# 08_BB_Processor.net
KiCad netlist of a schematic drawn in Altium Designer
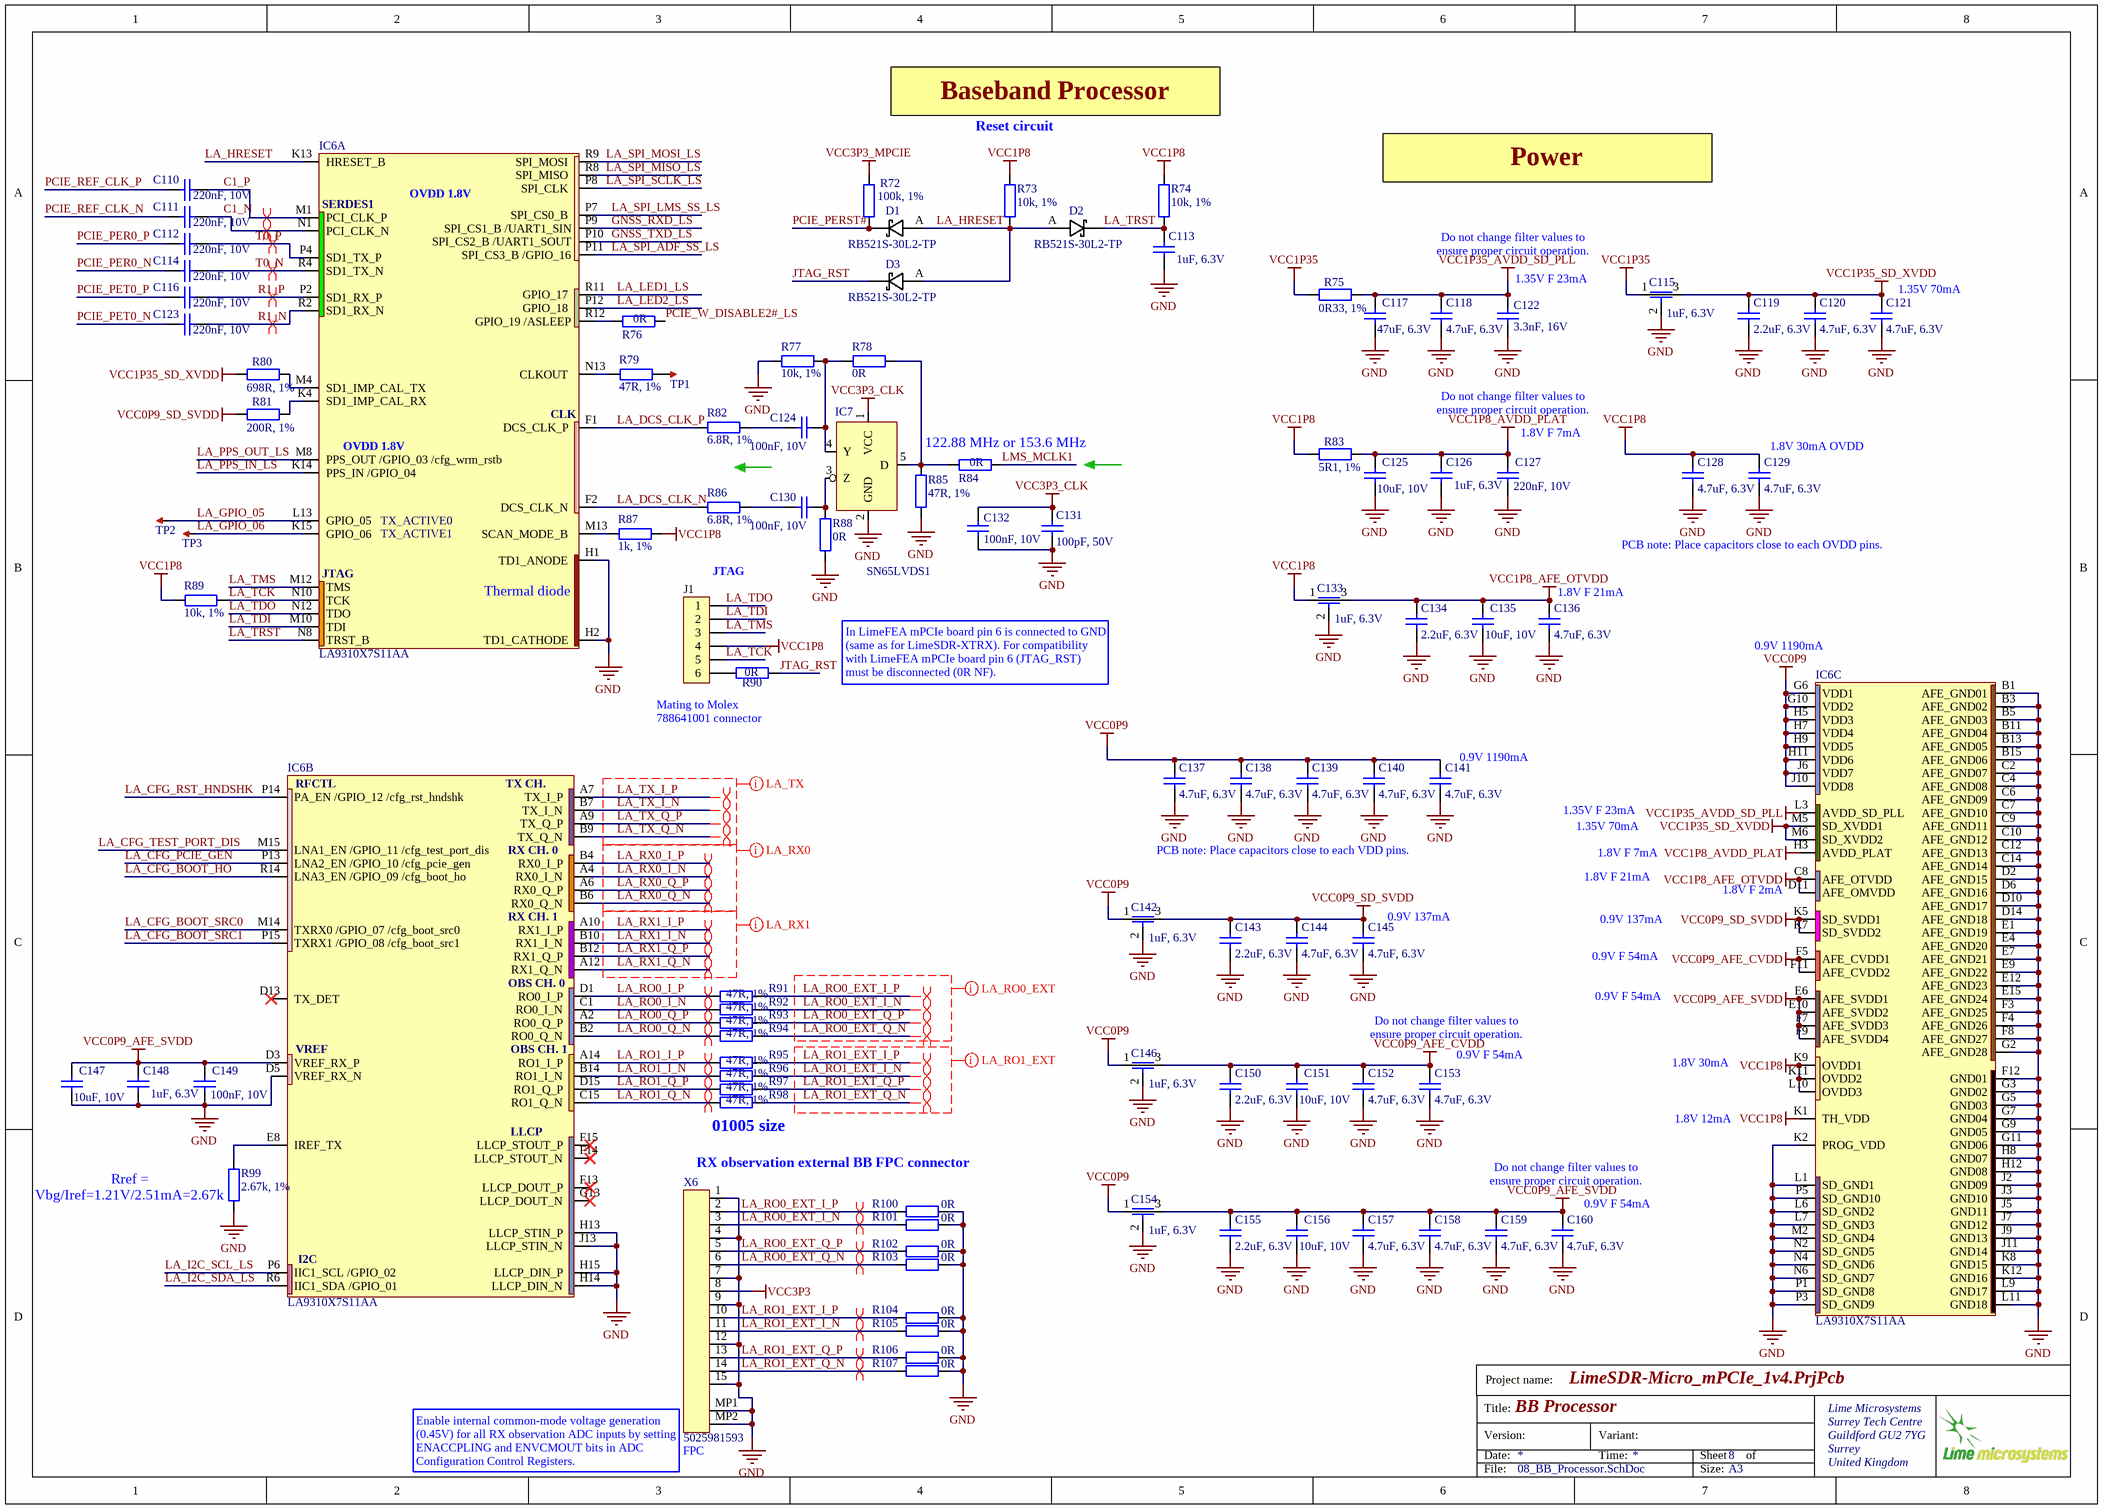
[diagram p0: 08_BB_Processor.SchDoc]

(export (version "E")
  (design (tool "Eeschema 10.0.6"))
  (components
    (comp (ref "C110")
      (value "220nF, 10V")
      (footprint "CAP0201")
      (fields
        (field (name "MANUFACTURER") "Murata")
        (field (name "TOLERANCE") "20%")
        (field (name "VOLTAGE") "10V")
      )
      (libsource (lib "LimeMicroAltiumLib_schLib") (part "Cap_0402"))
    )
    (comp (ref "C111")
      (value "220nF, 10V")
      (footprint "CAP0201")
      (fields
        (field (name "MANUFACTURER") "Murata")
        (field (name "TOLERANCE") "20%")
        (field (name "VOLTAGE") "10V")
      )
      (libsource (lib "LimeMicroAltiumLib_schLib") (part "Cap_0402"))
    )
    (comp (ref "C112")
      (value "220nF, 10V")
      (footprint "CAP0201")
      (fields
        (field (name "MANUFACTURER") "Murata")
        (field (name "TOLERANCE") "20%")
        (field (name "VOLTAGE") "10V")
      )
      (libsource (lib "LimeMicroAltiumLib_schLib") (part "Cap_0402"))
    )
    (comp (ref "C113")
      (value "1uF, 6.3V")
      (footprint "CAP0201")
      (fields (field (name "TOLERANCE") "±20%") (field (name "MANUFACTURER") "TDK Corporation"))
      (libsource (lib "LimeMicroAltiumLib_schLib") (part "Cap_0402"))
    )
    (comp (ref "C114")
      (value "220nF, 10V")
      (footprint "CAP0201")
      (fields
        (field (name "MANUFACTURER") "Murata")
        (field (name "TOLERANCE") "20%")
        (field (name "VOLTAGE") "10V")
      )
      (libsource (lib "LimeMicroAltiumLib_schLib") (part "Cap_0402"))
    )
    (comp (ref "C115")
      (value "1uF, 6.3V")
      (footprint "CAP0603_FEEDTHROUGH")
      (fields (field (name "MANUFACTURER") "TDK"))
      (libsource (lib "LimeMicroAltiumLib_schLib_r01") (part "Cap_feed_through"))
    )
    (comp (ref "C116")
      (value "220nF, 10V")
      (footprint "CAP0201")
      (fields
        (field (name "MANUFACTURER") "Murata")
        (field (name "TOLERANCE") "20%")
        (field (name "VOLTAGE") "10V")
      )
      (libsource (lib "LimeMicroAltiumLib_schLib") (part "Cap_0402"))
    )
    (comp (ref "C117")
      (value "47uF, 6.3V")
      (footprint "CAP0603")
      (fields (field (name "MANUFACTURER") "Murata") (field (name "TOLERANCE") "20%"))
      (libsource (lib "LimeFPGAboard_schLib") (part "Cap_0603"))
    )
    (comp (ref "C118")
      (value "4.7uF, 6.3V")
      (footprint "CAP0201")
      (fields (field (name "MANUFACTURER") "Murata") (field (name "TOLERANCE") "20%"))
      (libsource (lib "LimeMicroAltiumLib_schLib") (part "Cap_0402"))
    )
    (comp (ref "C119")
      (value "2.2uF, 6.3V")
      (footprint "CAP0201")
      (fields (field (name "MANUFACTURER") "Murata") (field (name "TOLERANCE") "20%"))
      (libsource (lib "LimeMicroAltiumLib_schLib") (part "Cap_0402"))
    )
    (comp (ref "C120")
      (value "4.7uF, 6.3V")
      (footprint "CAP0201")
      (fields (field (name "MANUFACTURER") "Murata") (field (name "TOLERANCE") "20%"))
      (libsource (lib "LimeMicroAltiumLib_schLib") (part "Cap_0402"))
    )
    (comp (ref "C121")
      (value "4.7uF, 6.3V")
      (footprint "CAP0201")
      (fields (field (name "MANUFACTURER") "Murata") (field (name "TOLERANCE") "20%"))
      (libsource (lib "LimeMicroAltiumLib_schLib") (part "Cap_0402"))
    )
    (comp (ref "C122")
      (value "3.3nF, 16V")
      (footprint "CAP0201")
      (fields (field (name "MANUFACTURER") "Murata"))
      (libsource (lib "LimeMicroAltiumLib_schLib") (part "Cap_0402"))
    )
    (comp (ref "C123")
      (value "220nF, 10V")
      (footprint "CAP0201")
      (fields
        (field (name "MANUFACTURER") "Murata")
        (field (name "TOLERANCE") "20%")
        (field (name "VOLTAGE") "10V")
      )
      (libsource (lib "LimeMicroAltiumLib_schLib") (part "Cap_0402"))
    )
    (comp (ref "C124")
      (value "100nF, 10V")
      (footprint "CAP0201")
      (fields (field (name "MANUFACTURER") "Samsung") (field (name "TOLERANCE") "20%"))
      (libsource (lib "LimeMicroAltiumLib_schLib") (part "Cap_0402"))
    )
    (comp (ref "C125")
      (value "10uF, 10V")
      (footprint "CAP0402")
      (fields (field (name "MANUFACTURER") "Murata"))
      (libsource (lib "LimeFPGAboard_schLib") (part "Cap_0603"))
    )
    (comp (ref "C126")
      (value "1uF, 6.3V")
      (footprint "CAP0201")
      (fields (field (name "TOLERANCE") "±20%") (field (name "MANUFACTURER") "TDK Corporation"))
      (libsource (lib "LimeMicroAltiumLib_schLib") (part "Cap_0402"))
    )
    (comp (ref "C127")
      (value "220nF, 10V")
      (footprint "CAP0201")
      (fields
        (field (name "MANUFACTURER") "Murata")
        (field (name "TOLERANCE") "20%")
        (field (name "VOLTAGE") "10V")
      )
      (libsource (lib "LimeMicroAltiumLib_schLib") (part "Cap_0402"))
    )
    (comp (ref "C128")
      (value "4.7uF, 6.3V")
      (footprint "CAP0201")
      (fields (field (name "MANUFACTURER") "Murata") (field (name "TOLERANCE") "20%"))
      (libsource (lib "LimeMicroAltiumLib_schLib") (part "Cap_0402"))
    )
    (comp (ref "C129")
      (value "4.7uF, 6.3V")
      (footprint "CAP0201")
      (fields (field (name "MANUFACTURER") "Murata") (field (name "TOLERANCE") "20%"))
      (libsource (lib "LimeMicroAltiumLib_schLib") (part "Cap_0402"))
    )
    (comp (ref "C130")
      (value "100nF, 10V")
      (footprint "CAP0201")
      (fields (field (name "MANUFACTURER") "Samsung") (field (name "TOLERANCE") "20%"))
      (libsource (lib "LimeMicroAltiumLib_schLib") (part "Cap_0402"))
    )
    (comp (ref "C131")
      (value "100pF, 50V")
      (footprint "CAP0201")
      (fields
        (field (name "MANUFACTURER") "TDK")
        (field (name "TOLERANCE") "5%")
        (field (name "VOLTAGE") "50V")
      )
      (libsource (lib "LimeMicroAltiumLib_schLib") (part "Cap_0402"))
    )
    (comp (ref "C132")
      (value "100nF, 10V")
      (footprint "CAP0201")
      (fields (field (name "MANUFACTURER") "Samsung") (field (name "TOLERANCE") "20%"))
      (libsource (lib "LimeMicroAltiumLib_schLib") (part "Cap_0402"))
    )
    (comp (ref "C133")
      (value "1uF, 6.3V")
      (footprint "CAP0603_FEEDTHROUGH")
      (fields (field (name "MANUFACTURER") "TDK"))
      (libsource (lib "LimeMicroAltiumLib_schLib_r01") (part "Cap_feed_through"))
    )
    (comp (ref "C134")
      (value "2.2uF, 6.3V")
      (footprint "CAP0201")
      (fields (field (name "MANUFACTURER") "Murata") (field (name "TOLERANCE") "20%"))
      (libsource (lib "LimeMicroAltiumLib_schLib") (part "Cap_0402"))
    )
    (comp (ref "C135")
      (value "10uF, 10V")
      (footprint "CAP0402")
      (fields (field (name "MANUFACTURER") "Murata"))
      (libsource (lib "LimeFPGAboard_schLib") (part "Cap_0603"))
    )
    (comp (ref "C136")
      (value "4.7uF, 6.3V")
      (footprint "CAP0201")
      (fields (field (name "MANUFACTURER") "Murata") (field (name "TOLERANCE") "20%"))
      (libsource (lib "LimeMicroAltiumLib_schLib") (part "Cap_0402"))
    )
    (comp (ref "C137")
      (value "4.7uF, 6.3V")
      (footprint "CAP0201")
      (fields (field (name "MANUFACTURER") "Murata") (field (name "TOLERANCE") "20%"))
      (libsource (lib "LimeMicroAltiumLib_schLib") (part "Cap_0402"))
    )
    (comp (ref "C138")
      (value "4.7uF, 6.3V")
      (footprint "CAP0201")
      (fields (field (name "MANUFACTURER") "Murata") (field (name "TOLERANCE") "20%"))
      (libsource (lib "LimeMicroAltiumLib_schLib") (part "Cap_0402"))
    )
    (comp (ref "C139")
      (value "4.7uF, 6.3V")
      (footprint "CAP0201")
      (fields (field (name "MANUFACTURER") "Murata") (field (name "TOLERANCE") "20%"))
      (libsource (lib "LimeMicroAltiumLib_schLib") (part "Cap_0402"))
    )
    (comp (ref "C140")
      (value "4.7uF, 6.3V")
      (footprint "CAP0201")
      (fields (field (name "MANUFACTURER") "Murata") (field (name "TOLERANCE") "20%"))
      (libsource (lib "LimeMicroAltiumLib_schLib") (part "Cap_0402"))
    )
    (comp (ref "C141")
      (value "4.7uF, 6.3V")
      (footprint "CAP0201")
      (fields (field (name "MANUFACTURER") "Murata") (field (name "TOLERANCE") "20%"))
      (libsource (lib "LimeMicroAltiumLib_schLib") (part "Cap_0402"))
    )
    (comp (ref "C142")
      (value "1uF, 6.3V")
      (footprint "CAP0603_FEEDTHROUGH")
      (fields (field (name "MANUFACTURER") "TDK"))
      (libsource (lib "LimeMicroAltiumLib_schLib_r01") (part "Cap_feed_through"))
    )
    (comp (ref "C143")
      (value "2.2uF, 6.3V")
      (footprint "CAP0201")
      (fields (field (name "MANUFACTURER") "Murata") (field (name "TOLERANCE") "20%"))
      (libsource (lib "LimeMicroAltiumLib_schLib") (part "Cap_0402"))
    )
    (comp (ref "C144")
      (value "4.7uF, 6.3V")
      (footprint "CAP0201")
      (fields (field (name "MANUFACTURER") "Murata") (field (name "TOLERANCE") "20%"))
      (libsource (lib "LimeMicroAltiumLib_schLib") (part "Cap_0402"))
    )
    (comp (ref "C145")
      (value "4.7uF, 6.3V")
      (footprint "CAP0201")
      (fields (field (name "MANUFACTURER") "Murata") (field (name "TOLERANCE") "20%"))
      (libsource (lib "LimeMicroAltiumLib_schLib") (part "Cap_0402"))
    )
    (comp (ref "C146")
      (value "1uF, 6.3V")
      (footprint "CAP0603_FEEDTHROUGH")
      (fields (field (name "MANUFACTURER") "TDK"))
      (libsource (lib "LimeMicroAltiumLib_schLib_r01") (part "Cap_feed_through"))
    )
    (comp (ref "C147")
      (value "10uF, 10V")
      (footprint "CAP0402")
      (fields (field (name "MANUFACTURER") "Murata"))
      (libsource (lib "LimeFPGAboard_schLib") (part "Cap_0603"))
    )
    (comp (ref "C148")
      (value "1uF, 6.3V")
      (footprint "CAP0201")
      (fields (field (name "TOLERANCE") "±20%") (field (name "MANUFACTURER") "TDK Corporation"))
      (libsource (lib "LimeMicroAltiumLib_schLib") (part "Cap_0402"))
    )
    (comp (ref "C149")
      (value "100nF, 10V")
      (footprint "CAP0201")
      (fields (field (name "MANUFACTURER") "Samsung") (field (name "TOLERANCE") "20%"))
      (libsource (lib "LimeMicroAltiumLib_schLib") (part "Cap_0402"))
    )
    (comp (ref "C150")
      (value "2.2uF, 6.3V")
      (footprint "CAP0201")
      (fields (field (name "MANUFACTURER") "Murata") (field (name "TOLERANCE") "20%"))
      (libsource (lib "LimeMicroAltiumLib_schLib") (part "Cap_0402"))
    )
    (comp (ref "C151")
      (value "10uF, 10V")
      (footprint "CAP0402")
      (fields (field (name "MANUFACTURER") "Murata"))
      (libsource (lib "LimeFPGAboard_schLib") (part "Cap_0603"))
    )
    (comp (ref "C152")
      (value "4.7uF, 6.3V")
      (footprint "CAP0201")
      (fields (field (name "MANUFACTURER") "Murata") (field (name "TOLERANCE") "20%"))
      (libsource (lib "LimeMicroAltiumLib_schLib") (part "Cap_0402"))
    )
    (comp (ref "C153")
      (value "4.7uF, 6.3V")
      (footprint "CAP0201")
      (fields (field (name "MANUFACTURER") "Murata") (field (name "TOLERANCE") "20%"))
      (libsource (lib "LimeMicroAltiumLib_schLib") (part "Cap_0402"))
    )
    (comp (ref "C154")
      (value "1uF, 6.3V")
      (footprint "CAP0603_FEEDTHROUGH")
      (fields (field (name "MANUFACTURER") "TDK"))
      (libsource (lib "LimeMicroAltiumLib_schLib_r01") (part "Cap_feed_through"))
    )
    (comp (ref "C155")
      (value "2.2uF, 6.3V")
      (footprint "CAP0201")
      (fields (field (name "MANUFACTURER") "Murata") (field (name "TOLERANCE") "20%"))
      (libsource (lib "LimeMicroAltiumLib_schLib") (part "Cap_0402"))
    )
    (comp (ref "C156")
      (value "10uF, 10V")
      (footprint "CAP0402")
      (fields (field (name "MANUFACTURER") "Murata"))
      (libsource (lib "LimeFPGAboard_schLib") (part "Cap_0603"))
    )
    (comp (ref "C157")
      (value "4.7uF, 6.3V")
      (footprint "CAP0201")
      (fields (field (name "MANUFACTURER") "Murata") (field (name "TOLERANCE") "20%"))
      (libsource (lib "LimeMicroAltiumLib_schLib") (part "Cap_0402"))
    )
    (comp (ref "C158")
      (value "4.7uF, 6.3V")
      (footprint "CAP0201")
      (fields (field (name "MANUFACTURER") "Murata") (field (name "TOLERANCE") "20%"))
      (libsource (lib "LimeMicroAltiumLib_schLib") (part "Cap_0402"))
    )
    (comp (ref "C159")
      (value "4.7uF, 6.3V")
      (footprint "CAP0201")
      (fields (field (name "MANUFACTURER") "Murata") (field (name "TOLERANCE") "20%"))
      (libsource (lib "LimeMicroAltiumLib_schLib") (part "Cap_0402"))
    )
    (comp (ref "C160")
      (value "4.7uF, 6.3V")
      (footprint "CAP0201")
      (fields (field (name "MANUFACTURER") "Murata") (field (name "TOLERANCE") "20%"))
      (libsource (lib "LimeMicroAltiumLib_schLib") (part "Cap_0402"))
    )
    (comp (ref "D1")
      (value "RB521S-30L2-TP")
      (footprint "RB521S-30L2-TP_DFN1006")
      (fields (field (name "MANUFACTURER") "MCC"))
      (libsource (lib "LimeMicroAltiumLib") (part "BAT46JFILM_shottky_diode"))
    )
    (comp (ref "D2")
      (value "RB521S-30L2-TP")
      (footprint "RB521S-30L2-TP_DFN1006")
      (fields (field (name "MANUFACTURER") "MCC"))
      (libsource (lib "LimeMicroAltiumLib") (part "BAT46JFILM_shottky_diode"))
    )
    (comp (ref "D3")
      (value "RB521S-30L2-TP")
      (footprint "RB521S-30L2-TP_DFN1006")
      (fields (field (name "MANUFACTURER") "MCC"))
      (libsource (lib "LimeMicroAltiumLib") (part "BAT46JFILM_shottky_diode"))
    )
    (comp (ref "IC6")
      (value "LA9310X7S11AA")
      (footprint "LA9310X7S11AA")
      (fields (field (name "MANUFACTURER") "NXP Semiconductors"))
      (libsource (lib "LimeMicroAltiumLib") (part "LA9310X7S11AA"))
    )
    (comp (ref "IC7")
      (value "SN65LVDS1")
      (footprint "SOT23-5_NO_SILK")
      (fields (field (name "MANUFACTURER") "TEXAS INSTRUMENTS"))
      (libsource (lib "LimeMicroAltiumLib_schLib") (part "SN65LVDS1"))
    )
    (comp (ref "J1")
      (value "Molex 0788641001")
      (footprint "Molex_0788641001_spring_contacts")
      (description "Header, 6-pin")
      (fields (field (name "MANUFACTURER") "Molex"))
      (libsource (lib "LimeMicroAltiumLib_schLib_r04") (part "Molex_0788641001_spring_contacts"))
    )
    (comp (ref "R72")
      (value "100k, 1%")
      (footprint "RES0201")
      (fields (field (name "MANUFACTURER") "Yageo") (field (name "TOLERANCE") "1%"))
      (libsource (lib "LimeFPGAboard_schLib") (part "Res_0402"))
    )
    (comp (ref "R73")
      (value "10k, 1%")
      (footprint "RES0201")
      (fields (field (name "MANUFACTURER") "Yageo") (field (name "TOLERANCE") "1%"))
      (libsource (lib "LimeFPGAboard_schLib") (part "Res_0402"))
    )
    (comp (ref "R74")
      (value "10k, 1%")
      (footprint "RES0201")
      (fields (field (name "MANUFACTURER") "Yageo") (field (name "TOLERANCE") "1%"))
      (libsource (lib "LimeFPGAboard_schLib") (part "Res_0402"))
    )
    (comp (ref "R75")
      (value "0R33, 1%")
      (footprint "RES0201")
      (fields (field (name "MANUFACTURER") "Ohmite"))
      (libsource (lib "LimeFPGAboard_schLib") (part "Res_0402"))
    )
    (comp (ref "R76")
      (value "0R")
      (footprint "RES0201")
      (fields (field (name "MANUFACTURER") "Yageo") (field (name "TOLERANCE") "5%"))
      (libsource (lib "LimeFPGAboard_schLib") (part "Res_0402"))
    )
    (comp (ref "R77")
      (value "10k, 1%")
      (footprint "RES0201")
      (fields (field (name "MANUFACTURER") "Yageo") (field (name "TOLERANCE") "1%"))
      (libsource (lib "LimeFPGAboard_schLib") (part "Res_0402"))
    )
    (comp (ref "R78")
      (value "0R")
      (footprint "RES0201")
      (fields (field (name "MANUFACTURER") "Yageo") (field (name "TOLERANCE") "5%"))
      (libsource (lib "LimeFPGAboard_schLib") (part "Res_0402"))
    )
    (comp (ref "R79")
      (value "47R, 1%")
      (footprint "RES0201")
      (fields (field (name "MANUFACTURER") "Yageo") (field (name "TOLERANCE") "1%"))
      (libsource (lib "LimeFPGAboard_schLib") (part "Res_0402"))
    )
    (comp (ref "R80")
      (value "698R, 1%")
      (footprint "RES0201")
      (fields (field (name "MANUFACTURER") "Yageo") (field (name "TOLERANCE") "1%"))
      (libsource (lib "LimeFPGAboard_schLib") (part "Res_0402"))
    )
    (comp (ref "R81")
      (value "200R, 1%")
      (footprint "RES0201")
      (fields (field (name "MANUFACTURER") "Yageo") (field (name "TOLERANCE") "1%"))
      (libsource (lib "LimeFPGAboard_schLib") (part "Res_0402"))
    )
    (comp (ref "R82")
      (value "6.8R, 1%")
      (footprint "RES0201")
      (fields (field (name "MANUFACTURER") "Yageo") (field (name "TOLERANCE") "1%"))
      (libsource (lib "LimeMicroAltiumLib_schLib") (part "Res_0402"))
    )
    (comp (ref "R83")
      (value "5R1, 1%")
      (footprint "RES0201")
      (fields (field (name "MANUFACTURER") "Yageo"))
      (libsource (lib "LimeFPGAboard_schLib") (part "Res_0402"))
    )
    (comp (ref "R84")
      (value "0R")
      (footprint "RES0201")
      (fields (field (name "MANUFACTURER") "Yageo") (field (name "TOLERANCE") "5%"))
      (libsource (lib "LimeFPGAboard_schLib") (part "Res_0402"))
    )
    (comp (ref "R85")
      (value "47R, 1%")
      (footprint "RES0201")
      (fields (field (name "MANUFACTURER") "Yageo") (field (name "TOLERANCE") "1%"))
      (libsource (lib "LimeFPGAboard_schLib") (part "Res_0402"))
    )
    (comp (ref "R86")
      (value "6.8R, 1%")
      (footprint "RES0201")
      (fields (field (name "MANUFACTURER") "Yageo") (field (name "TOLERANCE") "1%"))
      (libsource (lib "LimeMicroAltiumLib_schLib") (part "Res_0402"))
    )
    (comp (ref "R87")
      (value "1k, 1%")
      (footprint "RES0201")
      (fields (field (name "MANUFACTURER") "Yageo") (field (name "TOLERANCE") "1%"))
      (libsource (lib "LimeMicroAltiumLib_schLib") (part "Res_0402"))
    )
    (comp (ref "R88")
      (value "0R")
      (footprint "RES0201")
      (fields (field (name "MANUFACTURER") "Yageo") (field (name "TOLERANCE") "5%"))
      (libsource (lib "LimeFPGAboard_schLib") (part "Res_0402"))
    )
    (comp (ref "R89")
      (value "10k, 1%")
      (footprint "RES0201")
      (fields (field (name "MANUFACTURER") "Yageo") (field (name "TOLERANCE") "1%"))
      (libsource (lib "LimeFPGAboard_schLib") (part "Res_0402"))
    )
    (comp (ref "R90")
      (value "0R")
      (footprint "RES0201")
      (fields (field (name "MANUFACTURER") "Yageo") (field (name "TOLERANCE") "5%"))
      (libsource (lib "LimeFPGAboard_schLib") (part "Res_0402"))
    )
    (comp (ref "R91")
      (value "47R, 1%")
      (footprint "RES01005")
      (fields (field (name "MANUFACTURER") "Yageo") (field (name "TOLERANCE") "1%"))
      (libsource (lib "LimeFPGAboard_schLib") (part "Res_0402"))
    )
    (comp (ref "R92")
      (value "47R, 1%")
      (footprint "RES01005")
      (fields (field (name "MANUFACTURER") "Yageo") (field (name "TOLERANCE") "1%"))
      (libsource (lib "LimeFPGAboard_schLib") (part "Res_0402"))
    )
    (comp (ref "R93")
      (value "47R, 1%")
      (footprint "RES01005")
      (fields (field (name "MANUFACTURER") "Yageo") (field (name "TOLERANCE") "1%"))
      (libsource (lib "LimeFPGAboard_schLib") (part "Res_0402"))
    )
    (comp (ref "R94")
      (value "47R, 1%")
      (footprint "RES01005")
      (fields (field (name "MANUFACTURER") "Yageo") (field (name "TOLERANCE") "1%"))
      (libsource (lib "LimeFPGAboard_schLib") (part "Res_0402"))
    )
    (comp (ref "R95")
      (value "47R, 1%")
      (footprint "RES01005")
      (fields (field (name "MANUFACTURER") "Yageo") (field (name "TOLERANCE") "1%"))
      (libsource (lib "LimeFPGAboard_schLib") (part "Res_0402"))
    )
    (comp (ref "R96")
      (value "47R, 1%")
      (footprint "RES01005")
      (fields (field (name "MANUFACTURER") "Yageo") (field (name "TOLERANCE") "1%"))
      (libsource (lib "LimeFPGAboard_schLib") (part "Res_0402"))
    )
    (comp (ref "R97")
      (value "47R, 1%")
      (footprint "RES01005")
      (fields (field (name "MANUFACTURER") "Yageo") (field (name "TOLERANCE") "1%"))
      (libsource (lib "LimeFPGAboard_schLib") (part "Res_0402"))
    )
    (comp (ref "R98")
      (value "47R, 1%")
      (footprint "RES01005")
      (fields (field (name "MANUFACTURER") "Yageo") (field (name "TOLERANCE") "1%"))
      (libsource (lib "LimeFPGAboard_schLib") (part "Res_0402"))
    )
    (comp (ref "R99")
      (value "2.67k, 1%")
      (footprint "RES0201")
      (fields (field (name "MANUFACTURER") "Stackpole Electronics") (field (name "TOLERANCE") "1%"))
      (libsource (lib "LimeFPGAboard_schLib") (part "Res_0402"))
    )
    (comp (ref "R100")
      (value "0R")
      (footprint "RES01005")
      (fields (field (name "MANUFACTURER") "Panasonic") (field (name "TOLERANCE") "5%"))
      (libsource (lib "LimeFPGAboard_schLib") (part "Res_0402"))
    )
    (comp (ref "R101")
      (value "0R")
      (footprint "RES01005")
      (fields (field (name "MANUFACTURER") "Panasonic") (field (name "TOLERANCE") "5%"))
      (libsource (lib "LimeFPGAboard_schLib") (part "Res_0402"))
    )
    (comp (ref "R102")
      (value "0R")
      (footprint "RES01005")
      (fields (field (name "MANUFACTURER") "Panasonic") (field (name "TOLERANCE") "5%"))
      (libsource (lib "LimeFPGAboard_schLib") (part "Res_0402"))
    )
    (comp (ref "R103")
      (value "0R")
      (footprint "RES01005")
      (fields (field (name "MANUFACTURER") "Panasonic") (field (name "TOLERANCE") "5%"))
      (libsource (lib "LimeFPGAboard_schLib") (part "Res_0402"))
    )
    (comp (ref "R104")
      (value "0R")
      (footprint "RES01005")
      (fields (field (name "MANUFACTURER") "Panasonic") (field (name "TOLERANCE") "5%"))
      (libsource (lib "LimeFPGAboard_schLib") (part "Res_0402"))
    )
    (comp (ref "R105")
      (value "0R")
      (footprint "RES01005")
      (fields (field (name "MANUFACTURER") "Panasonic") (field (name "TOLERANCE") "5%"))
      (libsource (lib "LimeFPGAboard_schLib") (part "Res_0402"))
    )
    (comp (ref "R106")
      (value "0R")
      (footprint "RES01005")
      (fields (field (name "MANUFACTURER") "Panasonic") (field (name "TOLERANCE") "5%"))
      (libsource (lib "LimeFPGAboard_schLib") (part "Res_0402"))
    )
    (comp (ref "R107")
      (value "0R")
      (footprint "RES01005")
      (fields (field (name "MANUFACTURER") "Panasonic") (field (name "TOLERANCE") "5%"))
      (libsource (lib "LimeFPGAboard_schLib") (part "Res_0402"))
    )
    (comp (ref "TP1")
      (value "TESTPOINT_PAD")
      (footprint "TP_PAD_1MM")
      (description "Test Point PCB mount Miniature White")
      (libsource (lib "LimeMicroAltiumLib_schLib_r04") (part "TESTPOINT_PAD"))
    )
    (comp (ref "TP2")
      (value "TESTPOINT_PAD")
      (footprint "TP_PAD_1MM")
      (description "Test Point PCB mount Miniature White")
      (libsource (lib "LimeMicroAltiumLib_schLib_r04") (part "TESTPOINT_PAD"))
    )
    (comp (ref "TP3")
      (value "TESTPOINT_PAD")
      (footprint "TP_PAD_1MM")
      (description "Test Point PCB mount Miniature White")
      (libsource (lib "LimeMicroAltiumLib_schLib_r04") (part "TESTPOINT_PAD"))
    )
    (comp (ref "X6")
      (value "5025981593")
      (footprint "5025981593_FPC_connector")
      (fields (field (name "MANUFACTURER") "Molex"))
      (libsource (lib "LimeMicroAltiumLib_schLib_r04") (part "5025981593_FPC_connector"))
    )
  )
  (nets
    (net (code "1") (name "/C1_N") (class "Default")
      (node (ref "C111") (pin "2") (pinfunction "2_2") (pintype "passive"))
      (node (ref "IC6") (pin "N1") (pinfunction "PCI_CLK_N_N1") (pintype "power_in"))
    )
    (net (code "2") (name "/C1_P") (class "Default")
      (node (ref "C110") (pin "2") (pinfunction "2_2") (pintype "passive"))
      (node (ref "IC6") (pin "M1") (pinfunction "PCI_CLK_P_M1") (pintype "power_in"))
    )
    (net (code "3") (name "/GNSS_RXD_LS") (class "Default")
      (node (ref "IC6") (pin "P9") (pinfunction "SPI_CS1_B_/UART1_SIN_P9") (pintype "power_in"))
    )
    (net (code "4") (name "/GNSS_TXD_LS") (class "Default")
      (node (ref "IC6") (pin "P10") (pinfunction "SPI_CS2_B_/UART1_SOUT_P10") (pintype "power_in"))
    )
    (net (code "5") (name "/JTAG_RST") (class "Default")
      (node (ref "D3") (pin "C") (pinfunction "C_C") (pintype "passive"))
      (node (ref "R90") (pin "2") (pinfunction "2_2") (pintype "passive"))
    )
    (net (code "6") (name "/LA_CFG_BOOT_HO") (class "Default")
      (node (ref "IC6") (pin "R14") (pinfunction "LNA3_EN_/GPIO_09_/cfg_boot_ho_R14") (pintype "power_in"))
    )
    (net (code "7") (name "/LA_CFG_BOOT_SRC0") (class "Default")
      (node (ref "IC6") (pin "M14") (pinfunction "TXRX0_/GPIO_07_/cfg_boot_src0_M14") (pintype "power_in"))
    )
    (net (code "8") (name "/LA_CFG_BOOT_SRC1") (class "Default")
      (node (ref "IC6") (pin "P15") (pinfunction "TXRX1_/GPIO_08_/cfg_boot_src1_P15") (pintype "power_in"))
    )
    (net (code "9") (name "/LA_CFG_PCIE_GEN") (class "Default")
      (node (ref "IC6") (pin "P13") (pinfunction "LNA2_EN_/GPIO_10_/cfg_pcie_gen_P13") (pintype "power_in"))
    )
    (net (code "10") (name "/LA_CFG_RST_HNDSHK") (class "Default")
      (node (ref "IC6") (pin "P14") (pinfunction "PA_EN_/GPIO_12_/cfg_rst_hndshk_P14") (pintype "power_in"))
    )
    (net (code "11") (name "/LA_CFG_TEST_PORT_DIS") (class "Default")
      (node (ref "IC6") (pin "M15") (pinfunction "LNA1_EN_/GPIO_11_/cfg_test_port_dis_M15") (pintype "power_in"))
    )
    (net (code "12") (name "/LA_DCS_CLK_N") (class "Default")
      (node (ref "IC6") (pin "F2") (pinfunction "DCS_CLK_N_F2") (pintype "power_in"))
      (node (ref "R86") (pin "2") (pinfunction "2_2") (pintype "passive"))
    )
    (net (code "13") (name "/LA_DCS_CLK_P") (class "Default")
      (node (ref "IC6") (pin "F1") (pinfunction "DCS_CLK_P_F1") (pintype "power_in"))
      (node (ref "R82") (pin "2") (pinfunction "2_2") (pintype "passive"))
    )
    (net (code "14") (name "/LA_GPIO_05") (class "Default")
      (node (ref "IC6") (pin "L13") (pinfunction "GPIO_05_L13") (pintype "power_in"))
      (node (ref "TP2") (pin "1") (pintype "passive"))
    )
    (net (code "15") (name "/LA_GPIO_06") (class "Default")
      (node (ref "IC6") (pin "K15") (pinfunction "GPIO_06_K15") (pintype "power_in"))
      (node (ref "TP3") (pin "1") (pintype "passive"))
    )
    (net (code "16") (name "/LA_HRESET") (class "Default")
      (node (ref "D1") (pin "A") (pinfunction "A_A") (pintype "passive"))
      (node (ref "D2") (pin "A") (pinfunction "A_A") (pintype "passive"))
      (node (ref "D3") (pin "A") (pinfunction "A_A") (pintype "passive"))
      (node (ref "IC6") (pin "K13") (pinfunction "HRESET_B_K13") (pintype "power_in"))
      (node (ref "R73") (pin "2") (pinfunction "2_2") (pintype "passive"))
    )
    (net (code "17") (name "/LA_I2C_SCL_LS") (class "Default")
      (node (ref "IC6") (pin "P6") (pinfunction "IIC1_SCL_/GPIO_02_P6") (pintype "power_in"))
    )
    (net (code "18") (name "/LA_I2C_SDA_LS") (class "Default")
      (node (ref "IC6") (pin "R6") (pinfunction "IIC1_SDA_/GPIO_01_R6") (pintype "power_in"))
    )
    (net (code "19") (name "/LA_LED1_LS") (class "Default")
      (node (ref "IC6") (pin "R11") (pinfunction "GPIO_17_R11") (pintype "power_in"))
    )
    (net (code "20") (name "/LA_LED2_LS") (class "Default")
      (node (ref "IC6") (pin "P12") (pinfunction "GPIO_18_P12") (pintype "power_in"))
    )
    (net (code "21") (name "/LA_PPS_IN_LS") (class "Default")
      (node (ref "IC6") (pin "K14") (pinfunction "PPS_IN_/GPIO_04_K14") (pintype "power_in"))
    )
    (net (code "22") (name "/LA_PPS_OUT_LS") (class "Default")
      (node (ref "IC6") (pin "M8") (pinfunction "PPS_OUT_/GPIO_03_/cfg_wrm_rstb_M8") (pintype "power_in"))
    )
    (net (code "23") (name "/LA_RO0_EXT_I_N") (class "Default")
      (node (ref "R101") (pin "1") (pinfunction "1_1") (pintype "passive"))
      (node (ref "R92") (pin "2") (pinfunction "2_2") (pintype "passive"))
      (node (ref "X6") (pin "3") (pinfunction "3_3") (pintype "passive"))
    )
    (net (code "24") (name "/LA_RO0_EXT_I_P") (class "Default")
      (node (ref "R100") (pin "1") (pinfunction "1_1") (pintype "passive"))
      (node (ref "R91") (pin "2") (pinfunction "2_2") (pintype "passive"))
      (node (ref "X6") (pin "2") (pinfunction "2_2") (pintype "passive"))
    )
    (net (code "25") (name "/LA_RO0_EXT_Q_N") (class "Default")
      (node (ref "R103") (pin "1") (pinfunction "1_1") (pintype "passive"))
      (node (ref "R94") (pin "2") (pinfunction "2_2") (pintype "passive"))
      (node (ref "X6") (pin "6") (pinfunction "6_6") (pintype "passive"))
    )
    (net (code "26") (name "/LA_RO0_EXT_Q_P") (class "Default")
      (node (ref "R102") (pin "1") (pinfunction "1_1") (pintype "passive"))
      (node (ref "R93") (pin "2") (pinfunction "2_2") (pintype "passive"))
      (node (ref "X6") (pin "5") (pinfunction "5_5") (pintype "passive"))
    )
    (net (code "27") (name "/LA_RO0_I_N") (class "Default")
      (node (ref "IC6") (pin "C1") (pinfunction "RO0_I_N_C1") (pintype "power_in"))
      (node (ref "R92") (pin "1") (pinfunction "1_1") (pintype "passive"))
    )
    (net (code "28") (name "/LA_RO0_I_P") (class "Default")
      (node (ref "IC6") (pin "D1") (pinfunction "RO0_I_P_D1") (pintype "power_in"))
      (node (ref "R91") (pin "1") (pinfunction "1_1") (pintype "passive"))
    )
    (net (code "29") (name "/LA_RO0_Q_N") (class "Default")
      (node (ref "IC6") (pin "B2") (pinfunction "RO0_Q_N_B2") (pintype "power_in"))
      (node (ref "R94") (pin "1") (pinfunction "1_1") (pintype "passive"))
    )
    (net (code "30") (name "/LA_RO0_Q_P") (class "Default")
      (node (ref "IC6") (pin "A2") (pinfunction "RO0_Q_P_A2") (pintype "power_in"))
      (node (ref "R93") (pin "1") (pinfunction "1_1") (pintype "passive"))
    )
    (net (code "31") (name "/LA_RO1_EXT_I_N") (class "Default")
      (node (ref "R105") (pin "1") (pinfunction "1_1") (pintype "passive"))
      (node (ref "R96") (pin "2") (pinfunction "2_2") (pintype "passive"))
      (node (ref "X6") (pin "11") (pinfunction "11_11") (pintype "passive"))
    )
    (net (code "32") (name "/LA_RO1_EXT_I_P") (class "Default")
      (node (ref "R104") (pin "1") (pinfunction "1_1") (pintype "passive"))
      (node (ref "R95") (pin "2") (pinfunction "2_2") (pintype "passive"))
      (node (ref "X6") (pin "10") (pinfunction "10_10") (pintype "passive"))
    )
    (net (code "33") (name "/LA_RO1_EXT_Q_N") (class "Default")
      (node (ref "R107") (pin "1") (pinfunction "1_1") (pintype "passive"))
      (node (ref "R98") (pin "2") (pinfunction "2_2") (pintype "passive"))
      (node (ref "X6") (pin "14") (pinfunction "14_14") (pintype "passive"))
    )
    (net (code "34") (name "/LA_RO1_EXT_Q_P") (class "Default")
      (node (ref "R106") (pin "1") (pinfunction "1_1") (pintype "passive"))
      (node (ref "R97") (pin "2") (pinfunction "2_2") (pintype "passive"))
      (node (ref "X6") (pin "13") (pinfunction "13_13") (pintype "passive"))
    )
    (net (code "35") (name "/LA_RO1_I_N") (class "Default")
      (node (ref "IC6") (pin "B14") (pinfunction "RO1_I_N_B14") (pintype "power_in"))
      (node (ref "R96") (pin "1") (pinfunction "1_1") (pintype "passive"))
    )
    (net (code "36") (name "/LA_RO1_I_P") (class "Default")
      (node (ref "IC6") (pin "A14") (pinfunction "RO1_I_P_A14") (pintype "power_in"))
      (node (ref "R95") (pin "1") (pinfunction "1_1") (pintype "passive"))
    )
    (net (code "37") (name "/LA_RO1_Q_N") (class "Default")
      (node (ref "IC6") (pin "C15") (pinfunction "RO1_Q_N_C15") (pintype "power_in"))
      (node (ref "R98") (pin "1") (pinfunction "1_1") (pintype "passive"))
    )
    (net (code "38") (name "/LA_RO1_Q_P") (class "Default")
      (node (ref "IC6") (pin "D15") (pinfunction "RO1_Q_P_D15") (pintype "power_in"))
      (node (ref "R97") (pin "1") (pinfunction "1_1") (pintype "passive"))
    )
    (net (code "39") (name "/LA_RX0_I_N") (class "Default")
      (node (ref "IC6") (pin "A4") (pinfunction "RX0_I_N_A4") (pintype "power_in"))
    )
    (net (code "40") (name "/LA_RX0_I_P") (class "Default")
      (node (ref "IC6") (pin "B4") (pinfunction "RX0_I_P_B4") (pintype "power_in"))
    )
    (net (code "41") (name "/LA_RX0_Q_N") (class "Default")
      (node (ref "IC6") (pin "B6") (pinfunction "RX0_Q_N_B6") (pintype "power_in"))
    )
    (net (code "42") (name "/LA_RX0_Q_P") (class "Default")
      (node (ref "IC6") (pin "A6") (pinfunction "RX0_Q_P_A6") (pintype "power_in"))
    )
    (net (code "43") (name "/LA_RX1_I_N") (class "Default")
      (node (ref "IC6") (pin "B10") (pinfunction "RX1_I_N_B10") (pintype "power_in"))
    )
    (net (code "44") (name "/LA_RX1_I_P") (class "Default")
      (node (ref "IC6") (pin "A10") (pinfunction "RX1_I_P_A10") (pintype "power_in"))
    )
    (net (code "45") (name "/LA_RX1_Q_N") (class "Default")
      (node (ref "IC6") (pin "A12") (pinfunction "RX1_Q_N_A12") (pintype "power_in"))
    )
    (net (code "46") (name "/LA_RX1_Q_P") (class "Default")
      (node (ref "IC6") (pin "B12") (pinfunction "RX1_Q_P_B12") (pintype "power_in"))
    )
    (net (code "47") (name "/LA_SPI_ADF_SS_LS") (class "Default")
      (node (ref "IC6") (pin "P11") (pinfunction "SPI_CS3_B_/GPIO_16_P11") (pintype "power_in"))
    )
    (net (code "48") (name "/LA_SPI_LMS_SS_LS") (class "Default")
      (node (ref "IC6") (pin "P7") (pinfunction "SPI_CS0_B_P7") (pintype "power_in"))
    )
    (net (code "49") (name "/LA_SPI_MISO_LS") (class "Default")
      (node (ref "IC6") (pin "R8") (pinfunction "SPI_MISO_R8") (pintype "power_in"))
    )
    (net (code "50") (name "/LA_SPI_MOSI_LS") (class "Default")
      (node (ref "IC6") (pin "R9") (pinfunction "SPI_MOSI_R9") (pintype "power_in"))
    )
    (net (code "51") (name "/LA_SPI_SCLK_LS") (class "Default")
      (node (ref "IC6") (pin "P8") (pinfunction "SPI_CLK_P8") (pintype "power_in"))
    )
    (net (code "52") (name "/LA_TCK") (class "Default")
      (node (ref "IC6") (pin "N10") (pinfunction "TCK_N10") (pintype "power_in"))
      (node (ref "J1") (pin "5") (pinfunction "5_5") (pintype "passive"))
      (node (ref "R89") (pin "2") (pinfunction "2_2") (pintype "passive"))
    )
    (net (code "53") (name "/LA_TDI") (class "Default")
      (node (ref "IC6") (pin "M10") (pinfunction "TDI_M10") (pintype "power_in"))
      (node (ref "J1") (pin "2") (pinfunction "2_2") (pintype "passive"))
    )
    (net (code "54") (name "/LA_TDO") (class "Default")
      (node (ref "IC6") (pin "N12") (pinfunction "TDO_N12") (pintype "power_in"))
      (node (ref "J1") (pin "1") (pinfunction "1_1") (pintype "passive"))
    )
    (net (code "55") (name "/LA_TMS") (class "Default")
      (node (ref "IC6") (pin "M12") (pinfunction "TMS_M12") (pintype "power_in"))
      (node (ref "J1") (pin "3") (pinfunction "3_3") (pintype "passive"))
    )
    (net (code "56") (name "/LA_TRST") (class "Default")
      (node (ref "C113") (pin "1") (pinfunction "1_1") (pintype "passive"))
      (node (ref "D2") (pin "C") (pinfunction "C_C") (pintype "passive"))
      (node (ref "IC6") (pin "N8") (pinfunction "TRST_B_N8") (pintype "power_in"))
      (node (ref "R74") (pin "2") (pinfunction "2_2") (pintype "passive"))
    )
    (net (code "57") (name "/LA_TX_I_N") (class "Default")
      (node (ref "IC6") (pin "B7") (pinfunction "TX_I_N_B7") (pintype "power_in"))
    )
    (net (code "58") (name "/LA_TX_I_P") (class "Default")
      (node (ref "IC6") (pin "A7") (pinfunction "TX_I_P_A7") (pintype "power_in"))
    )
    (net (code "59") (name "/LA_TX_Q_N") (class "Default")
      (node (ref "IC6") (pin "B9") (pinfunction "TX_Q_N_B9") (pintype "power_in"))
    )
    (net (code "60") (name "/LA_TX_Q_P") (class "Default")
      (node (ref "IC6") (pin "A9") (pinfunction "TX_Q_P_A9") (pintype "power_in"))
    )
    (net (code "61") (name "/LMS_MCLK1") (class "Default")
      (node (ref "R84") (pin "1") (pinfunction "1_1") (pintype "passive"))
    )
    (net (code "62") (name "/PCIE_PER0_N") (class "Default")
      (node (ref "C114") (pin "1") (pinfunction "1_1") (pintype "passive"))
    )
    (net (code "63") (name "/PCIE_PER0_P") (class "Default")
      (node (ref "C112") (pin "1") (pinfunction "1_1") (pintype "passive"))
    )
    (net (code "64") (name "/PCIE_PERST#") (class "Default")
      (node (ref "D1") (pin "C") (pinfunction "C_C") (pintype "passive"))
      (node (ref "R72") (pin "2") (pinfunction "2_2") (pintype "passive"))
    )
    (net (code "65") (name "/PCIE_PET0_N") (class "Default")
      (node (ref "C123") (pin "1") (pinfunction "1_1") (pintype "passive"))
    )
    (net (code "66") (name "/PCIE_PET0_P") (class "Default")
      (node (ref "C116") (pin "1") (pinfunction "1_1") (pintype "passive"))
    )
    (net (code "67") (name "/PCIE_REF_CLK_N") (class "Default")
      (node (ref "C111") (pin "1") (pinfunction "1_1") (pintype "passive"))
    )
    (net (code "68") (name "/PCIE_REF_CLK_P") (class "Default")
      (node (ref "C110") (pin "1") (pinfunction "1_1") (pintype "passive"))
    )
    (net (code "69") (name "/PCIE_W_DISABLE2#_LS") (class "Default")
      (node (ref "R76") (pin "1") (pinfunction "1_1") (pintype "passive"))
    )
    (net (code "70") (name "/R1_N") (class "Default")
      (node (ref "C123") (pin "2") (pinfunction "2_2") (pintype "passive"))
      (node (ref "IC6") (pin "R2") (pinfunction "SD1_RX_N_R2") (pintype "power_in"))
    )
    (net (code "71") (name "/R1_P") (class "Default")
      (node (ref "C116") (pin "2") (pinfunction "2_2") (pintype "passive"))
      (node (ref "IC6") (pin "P2") (pinfunction "SD1_RX_P_P2") (pintype "power_in"))
    )
    (net (code "72") (name "/T0_N") (class "Default")
      (node (ref "C114") (pin "2") (pinfunction "2_2") (pintype "passive"))
      (node (ref "IC6") (pin "R4") (pinfunction "SD1_TX_N_R4") (pintype "power_in"))
    )
    (net (code "73") (name "/T0_P") (class "Default")
      (node (ref "C112") (pin "2") (pinfunction "2_2") (pintype "passive"))
      (node (ref "IC6") (pin "P4") (pinfunction "SD1_TX_P_P4") (pintype "power_in"))
    )
    (net (code "74") (name "GND") (class "Default")
      (node (ref "C113") (pin "2") (pinfunction "2_2") (pintype "passive"))
      (node (ref "C115") (pin "2") (pinfunction "2_2") (pintype "passive"))
      (node (ref "C117") (pin "1") (pinfunction "1_1") (pintype "passive"))
      (node (ref "C118") (pin "1") (pinfunction "1_1") (pintype "passive"))
      (node (ref "C119") (pin "1") (pinfunction "1_1") (pintype "passive"))
      (node (ref "C120") (pin "1") (pinfunction "1_1") (pintype "passive"))
      (node (ref "C121") (pin "1") (pinfunction "1_1") (pintype "passive"))
      (node (ref "C122") (pin "2") (pinfunction "2_2") (pintype "passive"))
      (node (ref "C125") (pin "1") (pinfunction "1_1") (pintype "passive"))
      (node (ref "C126") (pin "2") (pinfunction "2_2") (pintype "passive"))
      (node (ref "C127") (pin "2") (pinfunction "2_2") (pintype "passive"))
      (node (ref "C128") (pin "1") (pinfunction "1_1") (pintype "passive"))
      (node (ref "C129") (pin "1") (pinfunction "1_1") (pintype "passive"))
      (node (ref "C131") (pin "1") (pinfunction "1_1") (pintype "passive"))
      (node (ref "C132") (pin "2") (pinfunction "2_2") (pintype "passive"))
      (node (ref "C133") (pin "2") (pinfunction "2_2") (pintype "passive"))
      (node (ref "C134") (pin "1") (pinfunction "1_1") (pintype "passive"))
      (node (ref "C135") (pin "1") (pinfunction "1_1") (pintype "passive"))
      (node (ref "C136") (pin "1") (pinfunction "1_1") (pintype "passive"))
      (node (ref "C137") (pin "1") (pinfunction "1_1") (pintype "passive"))
      (node (ref "C138") (pin "1") (pinfunction "1_1") (pintype "passive"))
      (node (ref "C139") (pin "1") (pinfunction "1_1") (pintype "passive"))
      (node (ref "C140") (pin "1") (pinfunction "1_1") (pintype "passive"))
      (node (ref "C141") (pin "1") (pinfunction "1_1") (pintype "passive"))
      (node (ref "C142") (pin "2") (pinfunction "2_2") (pintype "passive"))
      (node (ref "C143") (pin "1") (pinfunction "1_1") (pintype "passive"))
      (node (ref "C144") (pin "1") (pinfunction "1_1") (pintype "passive"))
      (node (ref "C145") (pin "1") (pinfunction "1_1") (pintype "passive"))
      (node (ref "C146") (pin "2") (pinfunction "2_2") (pintype "passive"))
      (node (ref "C147") (pin "1") (pinfunction "1_1") (pintype "passive"))
      (node (ref "C148") (pin "2") (pinfunction "2_2") (pintype "passive"))
      (node (ref "C149") (pin "2") (pinfunction "2_2") (pintype "passive"))
      (node (ref "C150") (pin "1") (pinfunction "1_1") (pintype "passive"))
      (node (ref "C151") (pin "1") (pinfunction "1_1") (pintype "passive"))
      (node (ref "C152") (pin "1") (pinfunction "1_1") (pintype "passive"))
      (node (ref "C153") (pin "1") (pinfunction "1_1") (pintype "passive"))
      (node (ref "C154") (pin "2") (pinfunction "2_2") (pintype "passive"))
      (node (ref "C155") (pin "1") (pinfunction "1_1") (pintype "passive"))
      (node (ref "C156") (pin "1") (pinfunction "1_1") (pintype "passive"))
      (node (ref "C157") (pin "1") (pinfunction "1_1") (pintype "passive"))
      (node (ref "C158") (pin "1") (pinfunction "1_1") (pintype "passive"))
      (node (ref "C159") (pin "1") (pinfunction "1_1") (pintype "passive"))
      (node (ref "C160") (pin "1") (pinfunction "1_1") (pintype "passive"))
      (node (ref "IC6") (pin "B1") (pinfunction "AFE_GND01_B1") (pintype "power_in"))
      (node (ref "IC6") (pin "B11") (pinfunction "AFE_GND04_B11") (pintype "power_in"))
      (node (ref "IC6") (pin "B13") (pinfunction "AFE_GND05_B13") (pintype "power_in"))
      (node (ref "IC6") (pin "B15") (pinfunction "AFE_GND06_B15") (pintype "power_in"))
      (node (ref "IC6") (pin "B3") (pinfunction "AFE_GND02_B3") (pintype "power_in"))
      (node (ref "IC6") (pin "B5") (pinfunction "AFE_GND03_B5") (pintype "power_in"))
      (node (ref "IC6") (pin "C10") (pinfunction "AFE_GND12_C10") (pintype "power_in"))
      (node (ref "IC6") (pin "C12") (pinfunction "AFE_GND13_C12") (pintype "power_in"))
      (node (ref "IC6") (pin "C14") (pinfunction "AFE_GND14_C14") (pintype "power_in"))
      (node (ref "IC6") (pin "C2") (pinfunction "AFE_GND07_C2") (pintype "power_in"))
      (node (ref "IC6") (pin "C4") (pinfunction "AFE_GND08_C4") (pintype "power_in"))
      (node (ref "IC6") (pin "C6") (pinfunction "AFE_GND09_C6") (pintype "power_in"))
      (node (ref "IC6") (pin "C7") (pinfunction "AFE_GND10_C7") (pintype "power_in"))
      (node (ref "IC6") (pin "C9") (pinfunction "AFE_GND11_C9") (pintype "power_in"))
      (node (ref "IC6") (pin "D10") (pinfunction "AFE_GND17_D10") (pintype "power_in"))
      (node (ref "IC6") (pin "D14") (pinfunction "AFE_GND18_D14") (pintype "power_in"))
      (node (ref "IC6") (pin "D2") (pinfunction "AFE_GND15_D2") (pintype "power_in"))
      (node (ref "IC6") (pin "D5") (pinfunction "VREF_RX_N_D5") (pintype "power_in"))
      (node (ref "IC6") (pin "D6") (pinfunction "AFE_GND16_D6") (pintype "power_in"))
      (node (ref "IC6") (pin "E1") (pinfunction "AFE_GND19_E1") (pintype "power_in"))
      (node (ref "IC6") (pin "E12") (pinfunction "AFE_GND23_E12") (pintype "power_in"))
      (node (ref "IC6") (pin "E15") (pinfunction "AFE_GND24_E15") (pintype "power_in"))
      (node (ref "IC6") (pin "E4") (pinfunction "AFE_GND20_E4") (pintype "power_in"))
      (node (ref "IC6") (pin "E7") (pinfunction "AFE_GND21_E7") (pintype "power_in"))
      (node (ref "IC6") (pin "E9") (pinfunction "AFE_GND22_E9") (pintype "power_in"))
      (node (ref "IC6") (pin "F12") (pinfunction "GND01_F12") (pintype "power_in"))
      (node (ref "IC6") (pin "F3") (pinfunction "AFE_GND25_F3") (pintype "power_in"))
      (node (ref "IC6") (pin "F4") (pinfunction "AFE_GND26_F4") (pintype "power_in"))
      (node (ref "IC6") (pin "F8") (pinfunction "AFE_GND27_F8") (pintype "power_in"))
      (node (ref "IC6") (pin "G11") (pinfunction "GND06_G11") (pintype "power_in"))
      (node (ref "IC6") (pin "G2") (pinfunction "AFE_GND28_G2") (pintype "power_in"))
      (node (ref "IC6") (pin "G3") (pinfunction "GND02_G3") (pintype "power_in"))
      (node (ref "IC6") (pin "G5") (pinfunction "GND03_G5") (pintype "power_in"))
      (node (ref "IC6") (pin "G7") (pinfunction "GND04_G7") (pintype "power_in"))
      (node (ref "IC6") (pin "G9") (pinfunction "GND05_G9") (pintype "power_in"))
      (node (ref "IC6") (pin "H1") (pinfunction "TD1_ANODE_H1") (pintype "power_in"))
      (node (ref "IC6") (pin "H12") (pinfunction "GND08_H12") (pintype "power_in"))
      (node (ref "IC6") (pin "H13") (pinfunction "LLCP_STIN_P_H13") (pintype "power_in"))
      (node (ref "IC6") (pin "H14") (pinfunction "LLCP_DIN_N_H14") (pintype "power_in"))
      (node (ref "IC6") (pin "H15") (pinfunction "LLCP_DIN_P_H15") (pintype "power_in"))
      (node (ref "IC6") (pin "H2") (pinfunction "TD1_CATHODE_H2") (pintype "power_in"))
      (node (ref "IC6") (pin "H8") (pinfunction "GND07_H8") (pintype "power_in"))
      (node (ref "IC6") (pin "J11") (pinfunction "GND14_J11") (pintype "power_in"))
      (node (ref "IC6") (pin "J13") (pinfunction "LLCP_STIN_N_J13") (pintype "power_in"))
      (node (ref "IC6") (pin "J2") (pinfunction "GND09_J2") (pintype "power_in"))
      (node (ref "IC6") (pin "J3") (pinfunction "GND10_J3") (pintype "power_in"))
      (node (ref "IC6") (pin "J5") (pinfunction "GND11_J5") (pintype "power_in"))
      (node (ref "IC6") (pin "J7") (pinfunction "GND12_J7") (pintype "power_in"))
      (node (ref "IC6") (pin "J9") (pinfunction "GND13_J9") (pintype "power_in"))
      (node (ref "IC6") (pin "K12") (pinfunction "GND16_K12") (pintype "power_in"))
      (node (ref "IC6") (pin "K2") (pinfunction "PROG_VDD_K2") (pintype "power_in"))
      (node (ref "IC6") (pin "K8") (pinfunction "GND15_K8") (pintype "power_in"))
      (node (ref "IC6") (pin "L1") (pinfunction "SD_GND1_L1") (pintype "power_in"))
      (node (ref "IC6") (pin "L11") (pinfunction "GND18_L11") (pintype "power_in"))
      (node (ref "IC6") (pin "L6") (pinfunction "SD_GND2_L6") (pintype "power_in"))
      (node (ref "IC6") (pin "L7") (pinfunction "SD_GND3_L7") (pintype "power_in"))
      (node (ref "IC6") (pin "L9") (pinfunction "GND17_L9") (pintype "power_in"))
      (node (ref "IC6") (pin "M2") (pinfunction "SD_GND4_M2") (pintype "power_in"))
      (node (ref "IC6") (pin "N2") (pinfunction "SD_GND5_N2") (pintype "power_in"))
      (node (ref "IC6") (pin "N4") (pinfunction "SD_GND6_N4") (pintype "power_in"))
      (node (ref "IC6") (pin "N6") (pinfunction "SD_GND7_N6") (pintype "power_in"))
      (node (ref "IC6") (pin "P1") (pinfunction "SD_GND8_P1") (pintype "power_in"))
      (node (ref "IC6") (pin "P3") (pinfunction "SD_GND9_P3") (pintype "power_in"))
      (node (ref "IC6") (pin "P5") (pinfunction "SD_GND10_P5") (pintype "power_in"))
      (node (ref "IC7") (pin "2") (pinfunction "GND_2") (pintype "passive"))
      (node (ref "R100") (pin "2") (pinfunction "2_2") (pintype "passive"))
      (node (ref "R101") (pin "2") (pinfunction "2_2") (pintype "passive"))
      (node (ref "R102") (pin "2") (pinfunction "2_2") (pintype "passive"))
      (node (ref "R103") (pin "2") (pinfunction "2_2") (pintype "passive"))
      (node (ref "R104") (pin "2") (pinfunction "2_2") (pintype "passive"))
      (node (ref "R105") (pin "2") (pinfunction "2_2") (pintype "passive"))
      (node (ref "R106") (pin "2") (pinfunction "2_2") (pintype "passive"))
      (node (ref "R107") (pin "2") (pinfunction "2_2") (pintype "passive"))
      (node (ref "R77") (pin "1") (pinfunction "1_1") (pintype "passive"))
      (node (ref "R85") (pin "2") (pinfunction "2_2") (pintype "passive"))
      (node (ref "R88") (pin "1") (pinfunction "1_1") (pintype "passive"))
      (node (ref "R99") (pin "2") (pinfunction "2_2") (pintype "passive"))
      (node (ref "X6") (pin "1") (pinfunction "1_1") (pintype "passive"))
      (node (ref "X6") (pin "12") (pinfunction "12_12") (pintype "passive"))
      (node (ref "X6") (pin "15") (pinfunction "15_15") (pintype "passive"))
      (node (ref "X6") (pin "4") (pinfunction "4_4") (pintype "passive"))
      (node (ref "X6") (pin "7") (pinfunction "7_7") (pintype "passive"))
      (node (ref "X6") (pin "9") (pinfunction "9_9") (pintype "passive"))
      (node (ref "X6") (pin "MP1") (pinfunction "MP1_MP1") (pintype "passive"))
      (node (ref "X6") (pin "MP2") (pinfunction "MP2_MP2") (pintype "passive"))
    )
    (net (code "75") (name "Net-(C124-Pad1)") (class "Default")
      (node (ref "C124") (pin "1") (pinfunction "1_1") (pintype "passive"))
      (node (ref "R82") (pin "1") (pinfunction "1_1") (pintype "passive"))
    )
    (net (code "76") (name "Net-(C130-Pad1)") (class "Default")
      (node (ref "C130") (pin "1") (pinfunction "1_1") (pintype "passive"))
      (node (ref "R86") (pin "1") (pinfunction "1_1") (pintype "passive"))
    )
    (net (code "77") (name "Net-(IC6A-CLKOUT)") (class "Default")
      (node (ref "IC6") (pin "N13") (pinfunction "CLKOUT_N13") (pintype "power_in"))
      (node (ref "R79") (pin "2") (pinfunction "2_2") (pintype "passive"))
    )
    (net (code "78") (name "Net-(IC6A-GPIO_19_{slash}ASLEEP)") (class "Default")
      (node (ref "IC6") (pin "R12") (pinfunction "GPIO_19_/ASLEEP_R12") (pintype "power_in"))
      (node (ref "R76") (pin "2") (pinfunction "2_2") (pintype "passive"))
    )
    (net (code "79") (name "Net-(IC6A-SCAN_MODE_B)") (class "Default")
      (node (ref "IC6") (pin "M13") (pinfunction "SCAN_MODE_B_M13") (pintype "power_in"))
      (node (ref "R87") (pin "1") (pinfunction "1_1") (pintype "passive"))
    )
    (net (code "80") (name "Net-(IC6A-SD1_IMP_CAL_RX)") (class "Default")
      (node (ref "IC6") (pin "K4") (pinfunction "SD1_IMP_CAL_RX_K4") (pintype "power_in"))
      (node (ref "R81") (pin "1") (pinfunction "1_1") (pintype "passive"))
    )
    (net (code "81") (name "Net-(IC6A-SD1_IMP_CAL_TX)") (class "Default")
      (node (ref "IC6") (pin "M4") (pinfunction "SD1_IMP_CAL_TX_M4") (pintype "power_in"))
      (node (ref "R80") (pin "1") (pinfunction "1_1") (pintype "passive"))
    )
    (net (code "82") (name "Net-(IC6B-IREF_TX)") (class "Default")
      (node (ref "IC6") (pin "E8") (pinfunction "IREF_TX_E8") (pintype "power_in"))
      (node (ref "R99") (pin "1") (pinfunction "1_1") (pintype "passive"))
    )
    (net (code "83") (name "Net-(IC7-D)") (class "Default")
      (node (ref "IC7") (pin "5") (pinfunction "D_5") (pintype "passive"))
      (node (ref "R78") (pin "1") (pinfunction "1_1") (pintype "passive"))
      (node (ref "R84") (pin "2") (pinfunction "2_2") (pintype "passive"))
      (node (ref "R85") (pin "1") (pinfunction "1_1") (pintype "passive"))
    )
    (net (code "84") (name "Net-(IC7-Y)") (class "Default")
      (node (ref "C124") (pin "2") (pinfunction "2_2") (pintype "passive"))
      (node (ref "IC7") (pin "4") (pinfunction "Y_4") (pintype "passive"))
      (node (ref "R77") (pin "2") (pinfunction "2_2") (pintype "passive"))
      (node (ref "R78") (pin "2") (pinfunction "2_2") (pintype "passive"))
    )
    (net (code "85") (name "Net-(IC7-Z)") (class "Default")
      (node (ref "C130") (pin "2") (pinfunction "2_2") (pintype "passive"))
      (node (ref "IC7") (pin "3") (pinfunction "Z_3") (pintype "passive"))
      (node (ref "R88") (pin "2") (pinfunction "2_2") (pintype "passive"))
    )
    (net (code "86") (name "Net-(J1-Pad6)") (class "Default")
      (node (ref "J1") (pin "6") (pinfunction "6_6") (pintype "passive"))
      (node (ref "R90") (pin "1") (pinfunction "1_1") (pintype "passive"))
    )
    (net (code "87") (name "Net-(R79-Pad1)") (class "Default")
      (node (ref "R79") (pin "1") (pinfunction "1_1") (pintype "passive"))
      (node (ref "TP1") (pin "1") (pintype "passive"))
    )
    (net (code "88") (name "VCC0P9") (class "Default")
      (node (ref "C137") (pin "2") (pinfunction "2_2") (pintype "passive"))
      (node (ref "C138") (pin "2") (pinfunction "2_2") (pintype "passive"))
      (node (ref "C139") (pin "2") (pinfunction "2_2") (pintype "passive"))
      (node (ref "C140") (pin "2") (pinfunction "2_2") (pintype "passive"))
      (node (ref "C141") (pin "2") (pinfunction "2_2") (pintype "passive"))
      (node (ref "C142") (pin "1") (pinfunction "1_1") (pintype "passive"))
      (node (ref "C146") (pin "1") (pinfunction "1_1") (pintype "passive"))
      (node (ref "C154") (pin "1") (pinfunction "1_1") (pintype "passive"))
      (node (ref "IC6") (pin "G10") (pinfunction "VDD2_G10") (pintype "power_in"))
      (node (ref "IC6") (pin "G6") (pinfunction "VDD1_G6") (pintype "power_in"))
      (node (ref "IC6") (pin "H11") (pinfunction "VDD6_H11") (pintype "power_in"))
      (node (ref "IC6") (pin "H5") (pinfunction "VDD3_H5") (pintype "power_in"))
      (node (ref "IC6") (pin "H7") (pinfunction "VDD4_H7") (pintype "power_in"))
      (node (ref "IC6") (pin "H9") (pinfunction "VDD5_H9") (pintype "power_in"))
      (node (ref "IC6") (pin "J10") (pinfunction "VDD8_J10") (pintype "power_in"))
      (node (ref "IC6") (pin "J6") (pinfunction "VDD7_J6") (pintype "power_in"))
    )
    (net (code "89") (name "VCC0P9_AFE_CVDD") (class "Default")
      (node (ref "C146") (pin "3") (pinfunction "3_3") (pintype "passive"))
      (node (ref "C150") (pin "2") (pinfunction "2_2") (pintype "passive"))
      (node (ref "C151") (pin "2") (pinfunction "2_2") (pintype "passive"))
      (node (ref "C152") (pin "2") (pinfunction "2_2") (pintype "passive"))
      (node (ref "C153") (pin "2") (pinfunction "2_2") (pintype "passive"))
      (node (ref "IC6") (pin "F11") (pinfunction "AFE_CVDD2_F11") (pintype "power_in"))
      (node (ref "IC6") (pin "F5") (pinfunction "AFE_CVDD1_F5") (pintype "power_in"))
    )
    (net (code "90") (name "VCC0P9_AFE_SVDD") (class "Default")
      (node (ref "C147") (pin "2") (pinfunction "2_2") (pintype "passive"))
      (node (ref "C148") (pin "1") (pinfunction "1_1") (pintype "passive"))
      (node (ref "C149") (pin "1") (pinfunction "1_1") (pintype "passive"))
      (node (ref "C154") (pin "3") (pinfunction "3_3") (pintype "passive"))
      (node (ref "C155") (pin "2") (pinfunction "2_2") (pintype "passive"))
      (node (ref "C156") (pin "2") (pinfunction "2_2") (pintype "passive"))
      (node (ref "C157") (pin "2") (pinfunction "2_2") (pintype "passive"))
      (node (ref "C158") (pin "2") (pinfunction "2_2") (pintype "passive"))
      (node (ref "C159") (pin "2") (pinfunction "2_2") (pintype "passive"))
      (node (ref "C160") (pin "2") (pinfunction "2_2") (pintype "passive"))
      (node (ref "IC6") (pin "D3") (pinfunction "VREF_RX_P_D3") (pintype "power_in"))
      (node (ref "IC6") (pin "E10") (pinfunction "AFE_SVDD2_E10") (pintype "power_in"))
      (node (ref "IC6") (pin "E6") (pinfunction "AFE_SVDD1_E6") (pintype "power_in"))
      (node (ref "IC6") (pin "F7") (pinfunction "AFE_SVDD3_F7") (pintype "power_in"))
      (node (ref "IC6") (pin "F9") (pinfunction "AFE_SVDD4_F9") (pintype "power_in"))
    )
    (net (code "91") (name "VCC0P9_SD_SVDD") (class "Default")
      (node (ref "C142") (pin "3") (pinfunction "3_3") (pintype "passive"))
      (node (ref "C143") (pin "2") (pinfunction "2_2") (pintype "passive"))
      (node (ref "C144") (pin "2") (pinfunction "2_2") (pintype "passive"))
      (node (ref "C145") (pin "2") (pinfunction "2_2") (pintype "passive"))
      (node (ref "IC6") (pin "K5") (pinfunction "SD_SVDD1_K5") (pintype "power_in"))
      (node (ref "IC6") (pin "K7") (pinfunction "SD_SVDD2_K7") (pintype "power_in"))
      (node (ref "R81") (pin "2") (pinfunction "2_2") (pintype "passive"))
    )
    (net (code "92") (name "VCC1P8") (class "Default")
      (node (ref "C128") (pin "2") (pinfunction "2_2") (pintype "passive"))
      (node (ref "C129") (pin "2") (pinfunction "2_2") (pintype "passive"))
      (node (ref "C133") (pin "1") (pinfunction "1_1") (pintype "passive"))
      (node (ref "IC6") (pin "K1") (pinfunction "TH_VDD_K1") (pintype "power_in"))
      (node (ref "IC6") (pin "K11") (pinfunction "OVDD2_K11") (pintype "power_in"))
      (node (ref "IC6") (pin "K9") (pinfunction "OVDD1_K9") (pintype "power_in"))
      (node (ref "IC6") (pin "L10") (pinfunction "OVDD3_L10") (pintype "power_in"))
      (node (ref "J1") (pin "4") (pinfunction "4_4") (pintype "passive"))
      (node (ref "R73") (pin "1") (pinfunction "1_1") (pintype "passive"))
      (node (ref "R74") (pin "1") (pinfunction "1_1") (pintype "passive"))
      (node (ref "R83") (pin "2") (pinfunction "2_2") (pintype "passive"))
      (node (ref "R87") (pin "2") (pinfunction "2_2") (pintype "passive"))
      (node (ref "R89") (pin "1") (pinfunction "1_1") (pintype "passive"))
    )
    (net (code "93") (name "VCC1P8_AFE_OTVDD") (class "Default")
      (node (ref "C133") (pin "3") (pinfunction "3_3") (pintype "passive"))
      (node (ref "C134") (pin "2") (pinfunction "2_2") (pintype "passive"))
      (node (ref "C135") (pin "2") (pinfunction "2_2") (pintype "passive"))
      (node (ref "C136") (pin "2") (pinfunction "2_2") (pintype "passive"))
      (node (ref "IC6") (pin "C8") (pinfunction "AFE_OTVDD_C8") (pintype "power_in"))
      (node (ref "IC6") (pin "D11") (pinfunction "AFE_OMVDD_D11") (pintype "power_in"))
    )
    (net (code "94") (name "VCC1P8_AVDD_PLAT") (class "Default")
      (node (ref "C125") (pin "2") (pinfunction "2_2") (pintype "passive"))
      (node (ref "C126") (pin "1") (pinfunction "1_1") (pintype "passive"))
      (node (ref "C127") (pin "1") (pinfunction "1_1") (pintype "passive"))
      (node (ref "IC6") (pin "H3") (pinfunction "AVDD_PLAT_H3") (pintype "power_in"))
      (node (ref "R83") (pin "1") (pinfunction "1_1") (pintype "passive"))
    )
    (net (code "95") (name "VCC1P35") (class "Default")
      (node (ref "C115") (pin "1") (pinfunction "1_1") (pintype "passive"))
      (node (ref "R75") (pin "2") (pinfunction "2_2") (pintype "passive"))
    )
    (net (code "96") (name "VCC1P35_AVDD_SD_PLL") (class "Default")
      (node (ref "C117") (pin "2") (pinfunction "2_2") (pintype "passive"))
      (node (ref "C118") (pin "2") (pinfunction "2_2") (pintype "passive"))
      (node (ref "C122") (pin "1") (pinfunction "1_1") (pintype "passive"))
      (node (ref "IC6") (pin "L3") (pinfunction "AVDD_SD_PLL_L3") (pintype "power_in"))
      (node (ref "R75") (pin "1") (pinfunction "1_1") (pintype "passive"))
    )
    (net (code "97") (name "VCC1P35_SD_XVDD") (class "Default")
      (node (ref "C115") (pin "3") (pinfunction "3_3") (pintype "passive"))
      (node (ref "C119") (pin "2") (pinfunction "2_2") (pintype "passive"))
      (node (ref "C120") (pin "2") (pinfunction "2_2") (pintype "passive"))
      (node (ref "C121") (pin "2") (pinfunction "2_2") (pintype "passive"))
      (node (ref "IC6") (pin "M5") (pinfunction "SD_XVDD1_M5") (pintype "power_in"))
      (node (ref "IC6") (pin "M6") (pinfunction "SD_XVDD2_M6") (pintype "power_in"))
      (node (ref "R80") (pin "2") (pinfunction "2_2") (pintype "passive"))
    )
    (net (code "98") (name "VCC3P3") (class "Default")
      (node (ref "X6") (pin "8") (pinfunction "8_8") (pintype "passive"))
    )
    (net (code "99") (name "VCC3P3_CLK") (class "Default")
      (node (ref "C131") (pin "2") (pinfunction "2_2") (pintype "passive"))
      (node (ref "C132") (pin "1") (pinfunction "1_1") (pintype "passive"))
      (node (ref "IC7") (pin "1") (pinfunction "VCC_1") (pintype "passive"))
    )
    (net (code "100") (name "VCC3P3_MPCIE") (class "Default")
      (node (ref "R72") (pin "1") (pinfunction "1_1") (pintype "passive"))
    )
    (net (code "101") (name "unconnected-(IC6B-LLCP_DOUT_N-PadG13)") (class "Default")
      (node (ref "IC6") (pin "G13") (pinfunction "LLCP_DOUT_N_G13") (pintype "power_in+no_connect"))
    )
    (net (code "102") (name "unconnected-(IC6B-LLCP_DOUT_P-PadF13)") (class "Default")
      (node (ref "IC6") (pin "F13") (pinfunction "LLCP_DOUT_P_F13") (pintype "power_in+no_connect"))
    )
    (net (code "103") (name "unconnected-(IC6B-LLCP_STOUT_N-PadF14)") (class "Default")
      (node (ref "IC6") (pin "F14") (pinfunction "LLCP_STOUT_N_F14") (pintype "power_in+no_connect"))
    )
    (net (code "104") (name "unconnected-(IC6B-LLCP_STOUT_P-PadF15)") (class "Default")
      (node (ref "IC6") (pin "F15") (pinfunction "LLCP_STOUT_P_F15") (pintype "power_in+no_connect"))
    )
    (net (code "105") (name "unconnected-(IC6B-TX_DET-PadD13)") (class "Default")
      (node (ref "IC6") (pin "D13") (pinfunction "TX_DET_D13") (pintype "power_in+no_connect"))
    )
  )
)
